# Digital_Attenuator_Amp.net
KiCad netlist of a schematic drawn in Altium Designer
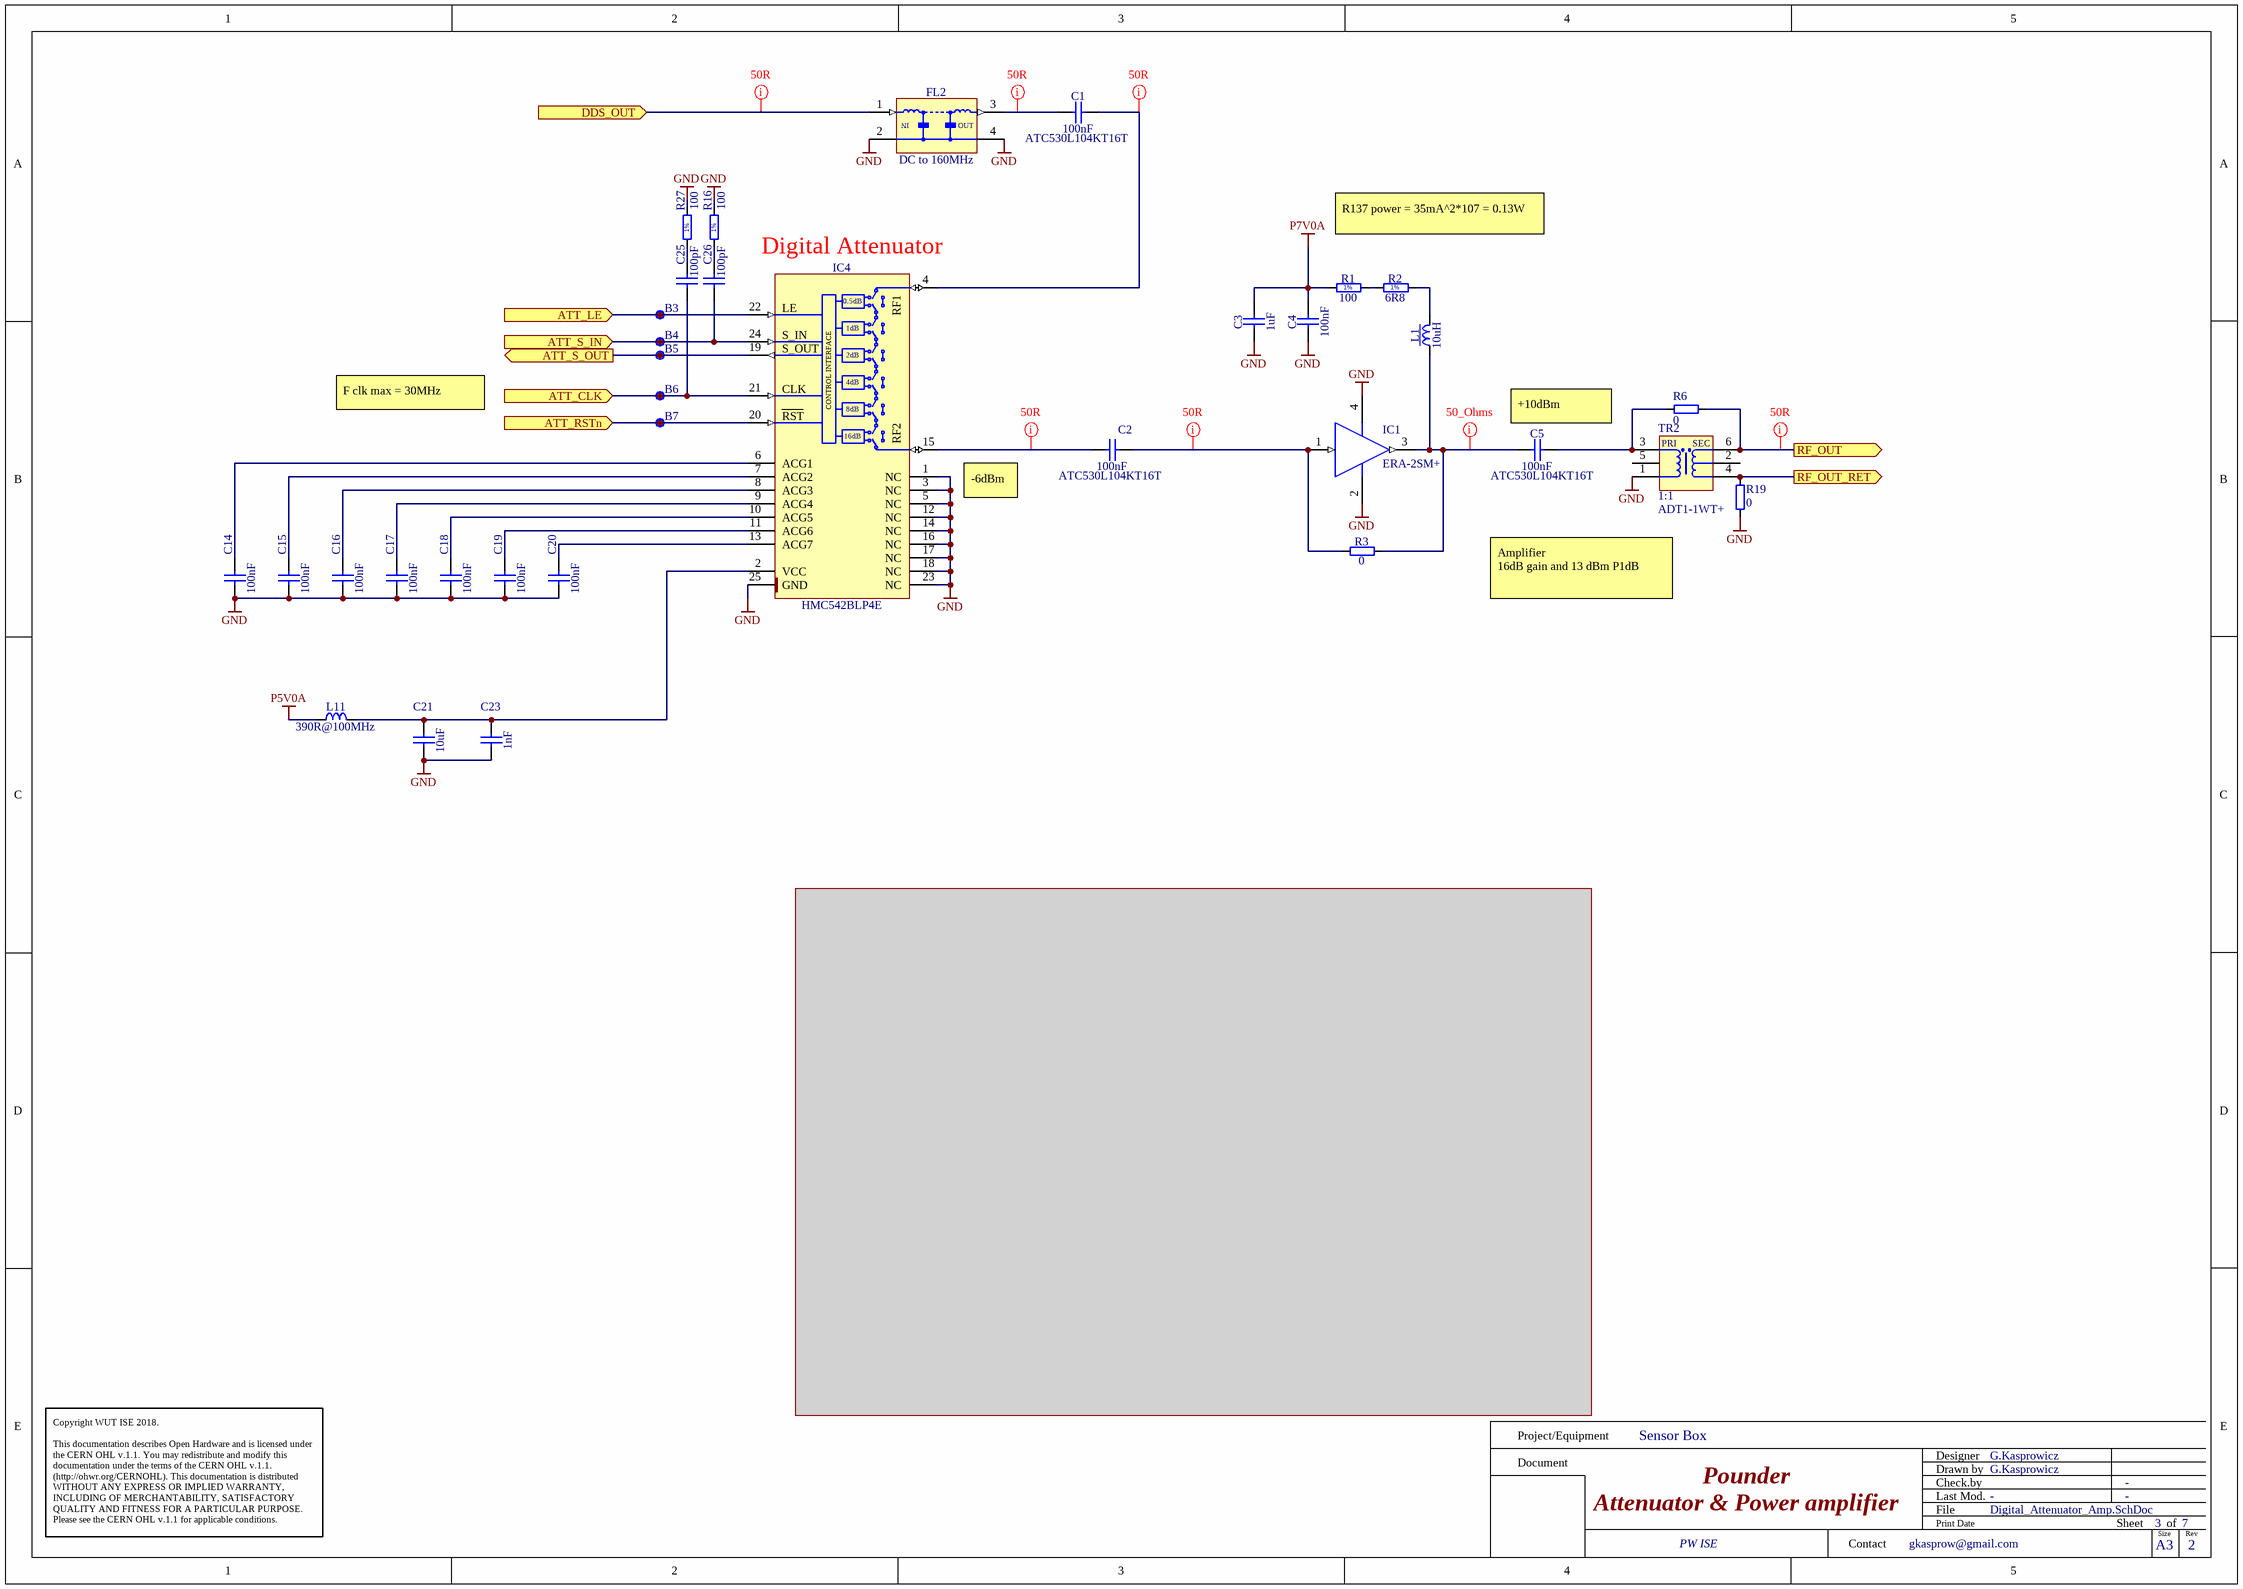
[diagram p0: Digital_Attenuator_Amp.SchDoc]

(export (version "E")
  (design (tool "Eeschema 10.0.6"))
  (components
    (comp (ref "B3")
      (value "SMD Pad")
      (footprint "C100")
      (description "Through Hole Pad")
      (fields (field (name "PART NUMBER") "SMD_PAD_D1MM") (field (name "AUTHOR") "CERN DEM JLC"))
      (libsource (lib "Eletro-mechanical") (part "Single SMD Pad (Round)"))
    )
    (comp (ref "B4")
      (value "SMD Pad")
      (footprint "C100")
      (description "Through Hole Pad")
      (fields (field (name "PART NUMBER") "SMD_PAD_D1MM") (field (name "AUTHOR") "CERN DEM JLC"))
      (libsource (lib "Eletro-mechanical") (part "Single SMD Pad (Round)"))
    )
    (comp (ref "B5")
      (value "SMD Pad")
      (footprint "C100")
      (description "Through Hole Pad")
      (fields (field (name "PART NUMBER") "SMD_PAD_D1MM") (field (name "AUTHOR") "CERN DEM JLC"))
      (libsource (lib "Eletro-mechanical") (part "Single SMD Pad (Round)"))
    )
    (comp (ref "B6")
      (value "SMD Pad")
      (footprint "C100")
      (description "Through Hole Pad")
      (fields (field (name "PART NUMBER") "SMD_PAD_D1MM") (field (name "AUTHOR") "CERN DEM JLC"))
      (libsource (lib "Eletro-mechanical") (part "Single SMD Pad (Round)"))
    )
    (comp (ref "B7")
      (value "SMD Pad")
      (footprint "C100")
      (description "Through Hole Pad")
      (fields (field (name "PART NUMBER") "SMD_PAD_D1MM") (field (name "AUTHOR") "CERN DEM JLC"))
      (libsource (lib "Eletro-mechanical") (part "Single SMD Pad (Round)"))
    )
    (comp (ref "C1")
      (value "100nF")
      (footprint "CAPC1005X70N")
      (description "Non-polarised capacitor")
      (fields
        (field (name "PART NUMBER") "CC0402_100NF_16V_10%_X7R_ATC_ATC530L")
        (field (name "VOLTAGE") "16V")
        (field (name "MANUFACTURER PART NUMBER") "ATC530L104KT16T")
        (field (name "AUTHOR") "CERN DEM BC")
      )
      (libsource (lib "Capacitors") (part "Capacitor - non polarized"))
    )
    (comp (ref "C2")
      (value "100nF")
      (footprint "CAPC1005X70N")
      (description "Non-polarised capacitor")
      (fields
        (field (name "PART NUMBER") "CC0402_100NF_16V_10%_X7R_ATC_ATC530L")
        (field (name "VOLTAGE") "16V")
        (field (name "MANUFACTURER PART NUMBER") "ATC530L104KT16T")
        (field (name "AUTHOR") "CERN DEM BC")
      )
      (libsource (lib "Capacitors") (part "Capacitor - non polarized"))
    )
    (comp (ref "C3")
      (value "1uF")
      (footprint "CAPC2012X140N")
      (description "Non-polarised capacitor")
      (fields
        (field (name "PART NUMBER") "CC0805_1UF_35V_20%_X7R")
        (field (name "VOLTAGE") "35V")
        (field (name "AUTHOR") "CERN DEM JLC")
      )
      (libsource (lib "Capacitors") (part "Capacitor - non polarized"))
    )
    (comp (ref "C4")
      (value "100nF")
      (footprint "CAPC1005X55N")
      (description "Non-polarised capacitor")
      (fields
        (field (name "PART NUMBER") "CC0402_100NF_16V_10%_X5R")
        (field (name "VOLTAGE") "16V")
        (field (name "AUTHOR") "CERN DEM JLC")
      )
      (libsource (lib "Capacitors") (part "Capacitor - non polarized"))
    )
    (comp (ref "C5")
      (value "100nF")
      (footprint "CAPC1005X70N")
      (description "Non-polarised capacitor")
      (fields
        (field (name "PART NUMBER") "CC0402_100NF_16V_10%_X7R_ATC_ATC530L")
        (field (name "VOLTAGE") "16V")
        (field (name "MANUFACTURER PART NUMBER") "ATC530L104KT16T")
        (field (name "AUTHOR") "CERN DEM BC")
      )
      (libsource (lib "Capacitors") (part "Capacitor - non polarized"))
    )
    (comp (ref "C14")
      (value "100nF")
      (footprint "CAPC1005X55N")
      (description "Non-polarised capacitor")
      (fields
        (field (name "PART NUMBER") "CC0402_100NF_16V_10%_X5R")
        (field (name "VOLTAGE") "16V")
        (field (name "AUTHOR") "CERN DEM JLC")
      )
      (libsource (lib "Capacitors") (part "Capacitor - non polarized"))
    )
    (comp (ref "C15")
      (value "100nF")
      (footprint "CAPC1005X55N")
      (description "Non-polarised capacitor")
      (fields
        (field (name "PART NUMBER") "CC0402_100NF_16V_10%_X5R")
        (field (name "VOLTAGE") "16V")
        (field (name "AUTHOR") "CERN DEM JLC")
      )
      (libsource (lib "Capacitors") (part "Capacitor - non polarized"))
    )
    (comp (ref "C16")
      (value "100nF")
      (footprint "CAPC1005X55N")
      (description "Non-polarised capacitor")
      (fields
        (field (name "PART NUMBER") "CC0402_100NF_16V_10%_X5R")
        (field (name "VOLTAGE") "16V")
        (field (name "AUTHOR") "CERN DEM JLC")
      )
      (libsource (lib "Capacitors") (part "Capacitor - non polarized"))
    )
    (comp (ref "C17")
      (value "100nF")
      (footprint "CAPC1005X55N")
      (description "Non-polarised capacitor")
      (fields
        (field (name "PART NUMBER") "CC0402_100NF_16V_10%_X5R")
        (field (name "VOLTAGE") "16V")
        (field (name "AUTHOR") "CERN DEM JLC")
      )
      (libsource (lib "Capacitors") (part "Capacitor - non polarized"))
    )
    (comp (ref "C18")
      (value "100nF")
      (footprint "CAPC1005X55N")
      (description "Non-polarised capacitor")
      (fields
        (field (name "PART NUMBER") "CC0402_100NF_16V_10%_X5R")
        (field (name "VOLTAGE") "16V")
        (field (name "AUTHOR") "CERN DEM JLC")
      )
      (libsource (lib "Capacitors") (part "Capacitor - non polarized"))
    )
    (comp (ref "C19")
      (value "100nF")
      (footprint "CAPC1005X55N")
      (description "Non-polarised capacitor")
      (fields
        (field (name "PART NUMBER") "CC0402_100NF_16V_10%_X5R")
        (field (name "VOLTAGE") "16V")
        (field (name "AUTHOR") "CERN DEM JLC")
      )
      (libsource (lib "Capacitors") (part "Capacitor - non polarized"))
    )
    (comp (ref "C20")
      (value "100nF")
      (footprint "CAPC1005X55N")
      (description "Non-polarised capacitor")
      (fields
        (field (name "PART NUMBER") "CC0402_100NF_16V_10%_X5R")
        (field (name "VOLTAGE") "16V")
        (field (name "AUTHOR") "CERN DEM JLC")
      )
      (libsource (lib "Capacitors") (part "Capacitor - non polarized"))
    )
    (comp (ref "C21")
      (value "10uF")
      (footprint "CAPC1608X80N")
      (description "Non-polarised capacitor")
      (fields
        (field (name "PART NUMBER") "CC0603_10UF_16V_20%_X5R")
        (field (name "VOLTAGE") "16V")
        (field (name "AUTHOR") "CERN DEM MR")
      )
      (libsource (lib "Capacitors") (part "Capacitor - non polarized"))
    )
    (comp (ref "C23")
      (value "1nF")
      (footprint "CAPC1005X55N")
      (description "Non-polarised capacitor")
      (fields
        (field (name "PART NUMBER") "CC0402_1NF_50V_10%_X7R")
        (field (name "VOLTAGE") "50V")
        (field (name "AUTHOR") "CERN DEM JLC")
      )
      (libsource (lib "Capacitors") (part "Capacitor - non polarized"))
    )
    (comp (ref "C25")
      (value "100pF")
      (footprint "CAPC1005X55N")
      (description "Non-polarised capacitor")
      (fields
        (field (name "PART NUMBER") "CC0402_100PF_50V_5%_C0G")
        (field (name "VOLTAGE") "50V")
        (field (name "AUTHOR") "CERN DEM JLC")
      )
      (libsource (lib "Capacitors") (part "Capacitor - non polarized"))
    )
    (comp (ref "C26")
      (value "100pF")
      (footprint "CAPC1005X55N")
      (description "Non-polarised capacitor")
      (fields
        (field (name "PART NUMBER") "CC0402_100PF_50V_5%_C0G")
        (field (name "VOLTAGE") "50V")
        (field (name "AUTHOR") "CERN DEM JLC")
      )
      (libsource (lib "Capacitors") (part "Capacitor - non polarized"))
    )
    (comp (ref "FL2")
      (value "DC to 160MHz")
      (footprint "FIL_MINI-CIRCUITS_FV1206")
      (description "50 Ohms DC to 160MHz Low Pass Filter")
      (fields
        (field (name "PART NUMBER") "FIL_MINI-CIRCUITS_LFCN-160+")
        (field (name "MANUFACTURER") "MINI-CIRCUITS")
        (field (name "AUTHOR") "CERN DEM MR")
      )
      (libsource (lib "Inductors & Transformers") (part "FIL_MINI-CIRCUITS_LFCN-160+"))
    )
    (comp (ref "IC1")
      (value "ERA-2SM+")
      (footprint "MINI-CIRCUITS_WW107")
      (description "Monolithic Amplifier")
      (fields (field (name "MANUFACTURER") "MINI-CIRCUITS") (field (name "AUTHOR") "CERN DEM JLC"))
      (libsource (lib "ICs And Semiconductors") (part "Monolithic Amplifier Type 1"))
    )
    (comp (ref "IC4")
      (value "HMC542BLP4E")
      (footprint "QFN50P400X400X100-25N-S295")
      (description "0.5dB LSB GaAs MMIC 6-bit Digital Serial Control Attenuator, DC - 4GHz")
      (fields (field (name "MANUFACTURER") "HITTITE MICROWAVE CORP") (field (name "AUTHOR") "CERN DEM JMW"))
      (libsource (lib "ICs And Semiconductors") (part "HMC542BLP4E"))
    )
    (comp (ref "L1")
      (value "10uH")
      (footprint "IND_MURATA_LQH32C")
      (description "Inductor With Core")
      (fields
        (field (name "PART NUMBER") "IND_10UH_10%_MURATA_LQH32CN100K33L")
        (field (name "POWER") "450mA")
        (field (name "AUTHOR") "CERN DEM JLC")
      )
      (libsource (lib "Inductors & Transformers") (part "Inductor With Magnetic core"))
    )
    (comp (ref "L11")
      (value "390R@100MHz")
      (footprint "INDC1608X95N")
      (description "Inductor")
      (fields
        (field (name "PART NUMBER") "IND0603_TDK_MPZ1608R391A")
        (field (name "POWER") "1.2A")
        (field (name "AUTHOR") "CERN DEM JLC")
      )
      (libsource (lib "Inductors & Transformers") (part "Inductor"))
    )
    (comp (ref "R1")
      (value "100")
      (footprint "RESC3216X65N")
      (description "Resistor - 1%")
      (fields
        (field (name "PART NUMBER") "R1206_100R_1%_0.5W_100PPM_VISHAY_CRCW-HP e3")
        (field (name "POWER") "0.5W")
        (field (name "AUTHOR") "CERN DEM JLC")
      )
      (libsource (lib "Resistors") (part "Resistor - 1%"))
    )
    (comp (ref "R2")
      (value "6R8")
      (footprint "RESC1608X55N")
      (description "Resistor - 1%")
      (fields
        (field (name "PART NUMBER") "R0603_6R8_1%_0.1W_200PPM")
        (field (name "POWER") "0.1W")
        (field (name "AUTHOR") "CERN DEM JLC")
      )
      (libsource (lib "Resistors") (part "Resistor - 1%"))
    )
    (comp (ref "R3")
      (value "0")
      (footprint "RESC1608X55N")
      (description "Resistor")
      (fields
        (field (name "PART NUMBER") "R0603_0R_JUMPER")
        (field (name "MANUFACTURER") "GENERIC")
        (field (name "AUTHOR") "CERN DEM JLC")
      )
      (libsource (lib "Resistors") (part "Resistor"))
    )
    (comp (ref "R6")
      (value "0")
      (footprint "RESC1005X40N")
      (description "Resistor")
      (fields
        (field (name "PART NUMBER") "R0402_0R_JUMPER")
        (field (name "MANUFACTURER") "GENERIC")
        (field (name "AUTHOR") "CERN DEM JLC")
      )
      (libsource (lib "Resistors") (part "Resistor"))
    )
    (comp (ref "R16")
      (value "100")
      (footprint "RESC1005X40N")
      (description "Resistor - 1%")
      (fields
        (field (name "PART NUMBER") "R0402_100R_1%_0.0625W_100PPM")
        (field (name "POWER") "0.0625W")
        (field (name "AUTHOR") "CERN DEM JLC")
      )
      (libsource (lib "Resistors") (part "Resistor - 1%"))
    )
    (comp (ref "R19")
      (value "0")
      (footprint "RESC1005X40N")
      (description "Resistor")
      (fields
        (field (name "PART NUMBER") "R0402_0R_JUMPER")
        (field (name "MANUFACTURER") "GENERIC")
        (field (name "AUTHOR") "CERN DEM JLC")
      )
      (libsource (lib "Resistors") (part "Resistor"))
    )
    (comp (ref "R27")
      (value "100")
      (footprint "RESC1005X40N")
      (description "Resistor - 1%")
      (fields
        (field (name "PART NUMBER") "R0402_100R_1%_0.0625W_100PPM")
        (field (name "POWER") "0.0625W")
        (field (name "AUTHOR") "CERN DEM JLC")
      )
      (libsource (lib "Resistors") (part "Resistor - 1%"))
    )
    (comp (ref "TR2")
      (value "1:1")
      (footprint "XFMR_MINI-CIRCUITS_CD542")
      (description "75 Ohm 0.4 To 800MHz RF Transformers")
      (fields
        (field (name "PART NUMBER") "XFMR_MINI-CIRCUITS_ADT1-1WT+")
        (field (name "MANUFACTURER") "MINI-CIRCUITS")
        (field (name "MANUFACTURER PART NUMBER") "ADT1-1WT+")
        (field (name "AUTHOR") "CERN DEM JLC")
      )
      (libsource (lib "Inductors & Transformers") (part "XFMR_MINI-CIRCUITS_ADT1-1WT+"))
    )
  )
  (nets
    (net (code "1") (name "/ATT_CLK") (class "Default")
      (node (ref "B6") (pin "1") (pinfunction "1_1") (pintype "bidirectional"))
      (node (ref "C25") (pin "2") (pinfunction "2_2") (pintype "passive"))
      (node (ref "IC4") (pin "21") (pinfunction "SHIFT_CLOCK_21") (pintype "input"))
    )
    (net (code "2") (name "/ATT_LE") (class "Default")
      (node (ref "B3") (pin "1") (pinfunction "1_1") (pintype "bidirectional"))
      (node (ref "IC4") (pin "22") (pinfunction "LATCH_ENABLE_22") (pintype "input"))
    )
    (net (code "3") (name "/ATT_RSTn") (class "Default")
      (node (ref "B7") (pin "1") (pinfunction "1_1") (pintype "bidirectional"))
      (node (ref "IC4") (pin "20") (pinfunction "~{RESET}_20") (pintype "input"))
    )
    (net (code "4") (name "/ATT_S_IN") (class "Default")
      (node (ref "B4") (pin "1") (pinfunction "1_1") (pintype "bidirectional"))
      (node (ref "C26") (pin "2") (pinfunction "2_2") (pintype "passive"))
      (node (ref "IC4") (pin "24") (pinfunction "SERIAL_INPUT_24") (pintype "input"))
    )
    (net (code "5") (name "/ATT_S_OUT") (class "Default")
      (node (ref "B5") (pin "1") (pinfunction "1_1") (pintype "bidirectional"))
      (node (ref "IC4") (pin "19") (pinfunction "SERIAL_OUTPUT_19") (pintype "output"))
    )
    (net (code "6") (name "/DDS_OUT") (class "Default")
      (node (ref "FL2") (pin "1") (pinfunction "RFIN_1") (pintype "input"))
    )
    (net (code "7") (name "/RF_OUT") (class "Default")
      (node (ref "R6") (pin "1") (pinfunction "1_1") (pintype "passive"))
      (node (ref "TR2") (pin "6") (pinfunction "SDOT_6") (pintype "passive"))
    )
    (net (code "8") (name "/RF_OUT_RET") (class "Default")
      (node (ref "R19") (pin "2") (pinfunction "2_2") (pintype "passive"))
      (node (ref "TR2") (pin "4") (pinfunction "S_4") (pintype "passive"))
    )
    (net (code "9") (name "GND") (class "Default")
      (node (ref "C14") (pin "1") (pinfunction "1_1") (pintype "passive"))
      (node (ref "C15") (pin "1") (pinfunction "1_1") (pintype "passive"))
      (node (ref "C16") (pin "1") (pinfunction "1_1") (pintype "passive"))
      (node (ref "C17") (pin "1") (pinfunction "1_1") (pintype "passive"))
      (node (ref "C18") (pin "1") (pinfunction "1_1") (pintype "passive"))
      (node (ref "C19") (pin "1") (pinfunction "1_1") (pintype "passive"))
      (node (ref "C20") (pin "1") (pinfunction "1_1") (pintype "passive"))
      (node (ref "C21") (pin "1") (pinfunction "1_1") (pintype "passive"))
      (node (ref "C23") (pin "1") (pinfunction "1_1") (pintype "passive"))
      (node (ref "C3") (pin "1") (pinfunction "1_1") (pintype "passive"))
      (node (ref "C4") (pin "1") (pinfunction "1_1") (pintype "passive"))
      (node (ref "FL2") (pin "2") (pinfunction "GND_2") (pintype "power_in"))
      (node (ref "FL2") (pin "4") (pinfunction "GND_4") (pintype "power_in"))
      (node (ref "IC1") (pin "2") (pinfunction "GND_2") (pintype "power_in"))
      (node (ref "IC1") (pin "4") (pinfunction "GND_4") (pintype "power_in"))
      (node (ref "IC4") (pin "1") (pinfunction "NC_1") (pintype "passive"))
      (node (ref "IC4") (pin "12") (pinfunction "NC_12") (pintype "passive"))
      (node (ref "IC4") (pin "14") (pinfunction "NC_14") (pintype "passive"))
      (node (ref "IC4") (pin "16") (pinfunction "NC_16") (pintype "passive"))
      (node (ref "IC4") (pin "17") (pinfunction "NC_17") (pintype "passive"))
      (node (ref "IC4") (pin "18") (pinfunction "NC_18") (pintype "passive"))
      (node (ref "IC4") (pin "23") (pinfunction "NC_23") (pintype "passive"))
      (node (ref "IC4") (pin "25") (pinfunction "GND_25") (pintype "power_in"))
      (node (ref "IC4") (pin "3") (pinfunction "NC_3") (pintype "passive"))
      (node (ref "IC4") (pin "5") (pinfunction "NC_5") (pintype "passive"))
      (node (ref "R16") (pin "2") (pinfunction "2_2") (pintype "passive"))
      (node (ref "R19") (pin "1") (pinfunction "1_1") (pintype "passive"))
      (node (ref "R27") (pin "2") (pinfunction "2_2") (pintype "passive"))
      (node (ref "TR2") (pin "1") (pinfunction "P_1") (pintype "passive"))
    )
    (net (code "10") (name "Net-(C25-Pad1)") (class "Default")
      (node (ref "C25") (pin "1") (pinfunction "1_1") (pintype "passive"))
      (node (ref "R27") (pin "1") (pinfunction "1_1") (pintype "passive"))
    )
    (net (code "11") (name "Net-(C26-Pad1)") (class "Default")
      (node (ref "C26") (pin "1") (pinfunction "1_1") (pintype "passive"))
      (node (ref "R16") (pin "1") (pinfunction "1_1") (pintype "passive"))
    )
    (net (code "12") (name "Net-(FL2-RFOUT)") (class "Default")
      (node (ref "C1") (pin "1") (pinfunction "1_1") (pintype "passive"))
      (node (ref "FL2") (pin "3") (pinfunction "RFOUT_3") (pintype "output"))
    )
    (net (code "13") (name "Net-(IC1-RF_IN)") (class "Default")
      (node (ref "C2") (pin "2") (pinfunction "2_2") (pintype "passive"))
      (node (ref "IC1") (pin "1") (pinfunction "RF_IN_1") (pintype "input"))
      (node (ref "R3") (pin "1") (pinfunction "1_1") (pintype "passive"))
    )
    (net (code "14") (name "Net-(IC1-RF_OUT)") (class "Default")
      (node (ref "C5") (pin "1") (pinfunction "1_1") (pintype "passive"))
      (node (ref "IC1") (pin "3") (pinfunction "RF_OUT_3") (pintype "output"))
      (node (ref "L1") (pin "1") (pinfunction "1_1") (pintype "passive"))
      (node (ref "R3") (pin "2") (pinfunction "2_2") (pintype "passive"))
    )
    (net (code "15") (name "Net-(IC4-ACG1)") (class "Default")
      (node (ref "C14") (pin "2") (pinfunction "2_2") (pintype "passive"))
      (node (ref "IC4") (pin "6") (pinfunction "ACG1_6") (pintype "passive"))
    )
    (net (code "16") (name "Net-(IC4-ACG2)") (class "Default")
      (node (ref "C15") (pin "2") (pinfunction "2_2") (pintype "passive"))
      (node (ref "IC4") (pin "7") (pinfunction "ACG2_7") (pintype "passive"))
    )
    (net (code "17") (name "Net-(IC4-ACG3)") (class "Default")
      (node (ref "C16") (pin "2") (pinfunction "2_2") (pintype "passive"))
      (node (ref "IC4") (pin "8") (pinfunction "ACG3_8") (pintype "passive"))
    )
    (net (code "18") (name "Net-(IC4-ACG4)") (class "Default")
      (node (ref "C17") (pin "2") (pinfunction "2_2") (pintype "passive"))
      (node (ref "IC4") (pin "9") (pinfunction "ACG4_9") (pintype "passive"))
    )
    (net (code "19") (name "Net-(IC4-ACG5)") (class "Default")
      (node (ref "C18") (pin "2") (pinfunction "2_2") (pintype "passive"))
      (node (ref "IC4") (pin "10") (pinfunction "ACG5_10") (pintype "passive"))
    )
    (net (code "20") (name "Net-(IC4-ACG6)") (class "Default")
      (node (ref "C19") (pin "2") (pinfunction "2_2") (pintype "passive"))
      (node (ref "IC4") (pin "11") (pinfunction "ACG6_11") (pintype "passive"))
    )
    (net (code "21") (name "Net-(IC4-ACG7)") (class "Default")
      (node (ref "C20") (pin "2") (pinfunction "2_2") (pintype "passive"))
      (node (ref "IC4") (pin "13") (pinfunction "ACG7_13") (pintype "passive"))
    )
    (net (code "22") (name "Net-(IC4-RF1)") (class "Default")
      (node (ref "C1") (pin "2") (pinfunction "2_2") (pintype "passive"))
      (node (ref "IC4") (pin "4") (pinfunction "RF1_4") (pintype "bidirectional"))
    )
    (net (code "23") (name "Net-(IC4-RF2)") (class "Default")
      (node (ref "C2") (pin "1") (pinfunction "1_1") (pintype "passive"))
      (node (ref "IC4") (pin "15") (pinfunction "RF2_15") (pintype "bidirectional"))
    )
    (net (code "24") (name "Net-(IC4-VCC)") (class "Default")
      (node (ref "C21") (pin "2") (pinfunction "2_2") (pintype "passive"))
      (node (ref "C23") (pin "2") (pinfunction "2_2") (pintype "passive"))
      (node (ref "IC4") (pin "2") (pinfunction "VCC_2") (pintype "power_in"))
      (node (ref "L11") (pin "2") (pinfunction "2_2") (pintype "passive"))
    )
    (net (code "25") (name "Net-(L1-Pad2)") (class "Default")
      (node (ref "L1") (pin "2") (pinfunction "2_2") (pintype "passive"))
      (node (ref "R2") (pin "2") (pinfunction "2_2") (pintype "passive"))
    )
    (net (code "26") (name "Net-(R1-Pad2)") (class "Default")
      (node (ref "R1") (pin "2") (pinfunction "2_2") (pintype "passive"))
      (node (ref "R2") (pin "1") (pinfunction "1_1") (pintype "passive"))
    )
    (net (code "27") (name "Net-(TR2-PDOT)") (class "Default")
      (node (ref "C5") (pin "2") (pinfunction "2_2") (pintype "passive"))
      (node (ref "R6") (pin "2") (pinfunction "2_2") (pintype "passive"))
      (node (ref "TR2") (pin "3") (pinfunction "PDOT_3") (pintype "passive"))
    )
    (net (code "28") (name "P5V0A") (class "Default")
      (node (ref "L11") (pin "1") (pinfunction "1_1") (pintype "passive"))
    )
    (net (code "29") (name "P7V0A") (class "Default")
      (node (ref "C3") (pin "2") (pinfunction "2_2") (pintype "passive"))
      (node (ref "C4") (pin "2") (pinfunction "2_2") (pintype "passive"))
      (node (ref "R1") (pin "1") (pinfunction "1_1") (pintype "passive"))
    )
    (net (code "30") (name "unconnected-(TR2-NC-Pad5)") (class "Default")
      (node (ref "TR2") (pin "5") (pinfunction "NC_5") (pintype "passive"))
    )
    (net (code "31") (name "unconnected-(TR2-SCT-Pad2)") (class "Default")
      (node (ref "TR2") (pin "2") (pinfunction "SCT_2") (pintype "passive"))
    )
  )
)
